# Qwiic_Pi_SHIM_S2.net
KiCad netlist of a schematic drawn in EAGLE
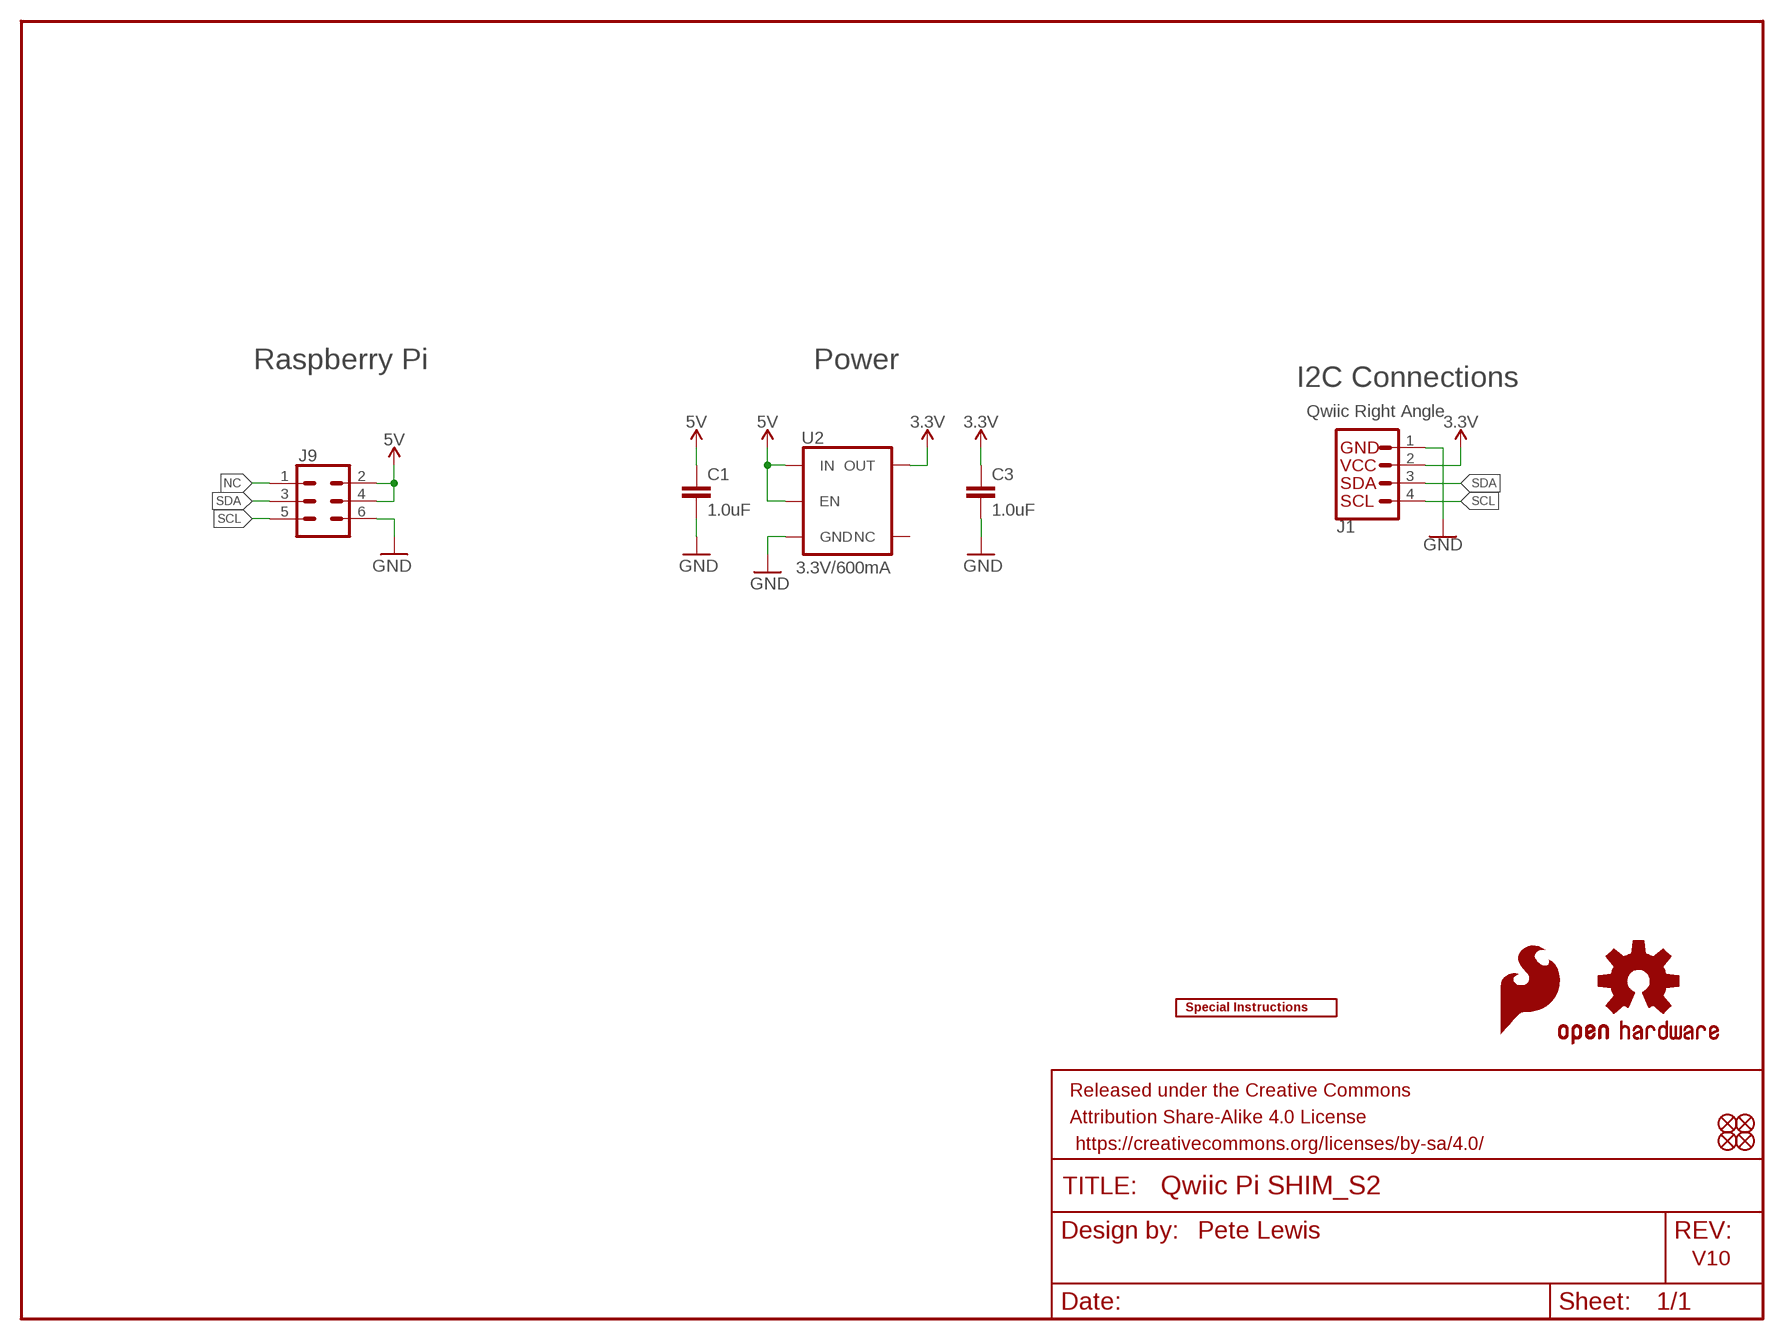
[diagram p0: schematic, sheet 1]

(export (version "E")
  (design (tool "Eeschema 10.0.6"))
  (components
    (comp (ref "C1")
      (value "1.0uF")
      (footprint "eagle-import:0603")
      (libsource (lib "eagle-import") (part "1.0UF-0603-16V-10%"))
    )
    (comp (ref "C3")
      (value "1.0uF")
      (footprint "eagle-import:0603")
      (libsource (lib "eagle-import") (part "1.0UF-0603-16V-10%"))
    )
    (comp (ref "FD1")
      (value "FIDUCIALUFIDUCIAL")
      (footprint "eagle-import:FIDUCIAL-MICRO")
      (libsource (lib "eagle-import") (part "FIDUCIALUFIDUCIAL"))
    )
    (comp (ref "FD2")
      (value "FIDUCIALUFIDUCIAL")
      (footprint "eagle-import:FIDUCIAL-MICRO")
      (libsource (lib "eagle-import") (part "FIDUCIALUFIDUCIAL"))
    )
    (comp (ref "FD3")
      (value "FIDUCIALUFIDUCIAL")
      (footprint "eagle-import:FIDUCIAL-MICRO")
      (libsource (lib "eagle-import") (part "FIDUCIALUFIDUCIAL"))
    )
    (comp (ref "FD4")
      (value "FIDUCIALUFIDUCIAL")
      (footprint "eagle-import:FIDUCIAL-MICRO")
      (libsource (lib "eagle-import") (part "FIDUCIALUFIDUCIAL"))
    )
    (comp (ref "FRAME1")
      (value "FRAME-LETTER")
      (footprint "eagle-import:CREATIVE_COMMONS")
      (libsource (lib "eagle-import") (part "FRAME-LETTER"))
    )
    (comp (ref "J1")
      (value "Qwiic Right Angle")
      (footprint "eagle-import:1X04_1MM_RA")
      (libsource (lib "eagle-import") (part "I2C_STANDARDQWIIC"))
    )
    (comp (ref "J9")
      (value "SPARKFUN-CONNECTORS_CONN_03X2SINGLE_SLOT-2MILS")
      (footprint "eagle-import:SPARKFUN-CONNECTORS_2X3-NS_PISHIM_LOCKING_SLOTS-2MILS")
      (libsource (lib "eagle-import") (part "SPARKFUN-CONNECTORS_CONN_03X2SINGLE_SLOT-2MILS"))
    )
    (comp (ref "LOGO1")
      (value "OSHW-LOGOMINI")
      (footprint "eagle-import:OSHW-LOGO-MINI")
      (libsource (lib "eagle-import") (part "OSHW-LOGOMINI"))
    )
    (comp (ref "U$1")
      (value "SFE_LOGO_FLAME.1_INCH")
      (footprint "eagle-import:SFE_LOGO_FLAME_.1")
      (libsource (lib "eagle-import") (part "SFE_LOGO_FLAME.1_INCH"))
    )
    (comp (ref "U$4")
      (value "SPECIAL_INSTRUCTIONS-ORDERING")
      (footprint "eagle-import:ORDERING_INSTRUCTIONS")
      (libsource (lib "eagle-import") (part "SPECIAL_INSTRUCTIONS-ORDERING"))
    )
    (comp (ref "U2")
      (value "3.3V/600mA")
      (footprint "eagle-import:SOT23-5")
      (libsource (lib "eagle-import") (part "V_REG_AP2112K-3.3V"))
    )
  )
  (nets
    (net (code "1") (name "3.3V") (class "Default")
      (node (ref "C3") (pin "1") (pinfunction "1_1") (pintype "passive"))
      (node (ref "J1") (pin "2") (pinfunction "2_2") (pintype "power_in"))
      (node (ref "U2") (pin "5") (pinfunction "OUT_5") (pintype "passive"))
    )
    (net (code "2") (name "5V") (class "Default")
      (node (ref "C1") (pin "1") (pinfunction "1_1") (pintype "passive"))
      (node (ref "J9") (pin "2") (pinfunction "2_2") (pintype "bidirectional"))
      (node (ref "J9") (pin "4") (pinfunction "4_4") (pintype "bidirectional"))
      (node (ref "U2") (pin "1") (pinfunction "IN_1") (pintype "input"))
      (node (ref "U2") (pin "3") (pinfunction "EN_3") (pintype "input"))
    )
    (net (code "3") (name "GND") (class "Default")
      (node (ref "C1") (pin "2") (pinfunction "2_2") (pintype "passive"))
      (node (ref "C3") (pin "2") (pinfunction "2_2") (pintype "passive"))
      (node (ref "J1") (pin "1") (pinfunction "1_1") (pintype "power_in"))
      (node (ref "J9") (pin "6") (pinfunction "6_6") (pintype "bidirectional"))
      (node (ref "U2") (pin "2") (pinfunction "GND_2") (pintype "input"))
    )
    (net (code "4") (name "NC") (class "Default")
      (node (ref "J9") (pin "1") (pinfunction "1_1") (pintype "bidirectional"))
    )
    (net (code "5") (name "SCL") (class "Default")
      (node (ref "J1") (pin "4") (pinfunction "4_4") (pintype "passive"))
      (node (ref "J9") (pin "5") (pinfunction "5_5") (pintype "bidirectional"))
    )
    (net (code "6") (name "SDA") (class "Default")
      (node (ref "J1") (pin "3") (pinfunction "3_3") (pintype "passive"))
      (node (ref "J9") (pin "3") (pinfunction "3_3") (pintype "bidirectional"))
    )
    (net (code "7") (name "unconnected-(U2-NC-Pad4)") (class "Default")
      (node (ref "U2") (pin "4") (pinfunction "NC_4") (pintype "no_connect"))
    )
  )
)
